# a202-4-band-eq.net
KiCad netlist of a schematic drawn in EAGLE
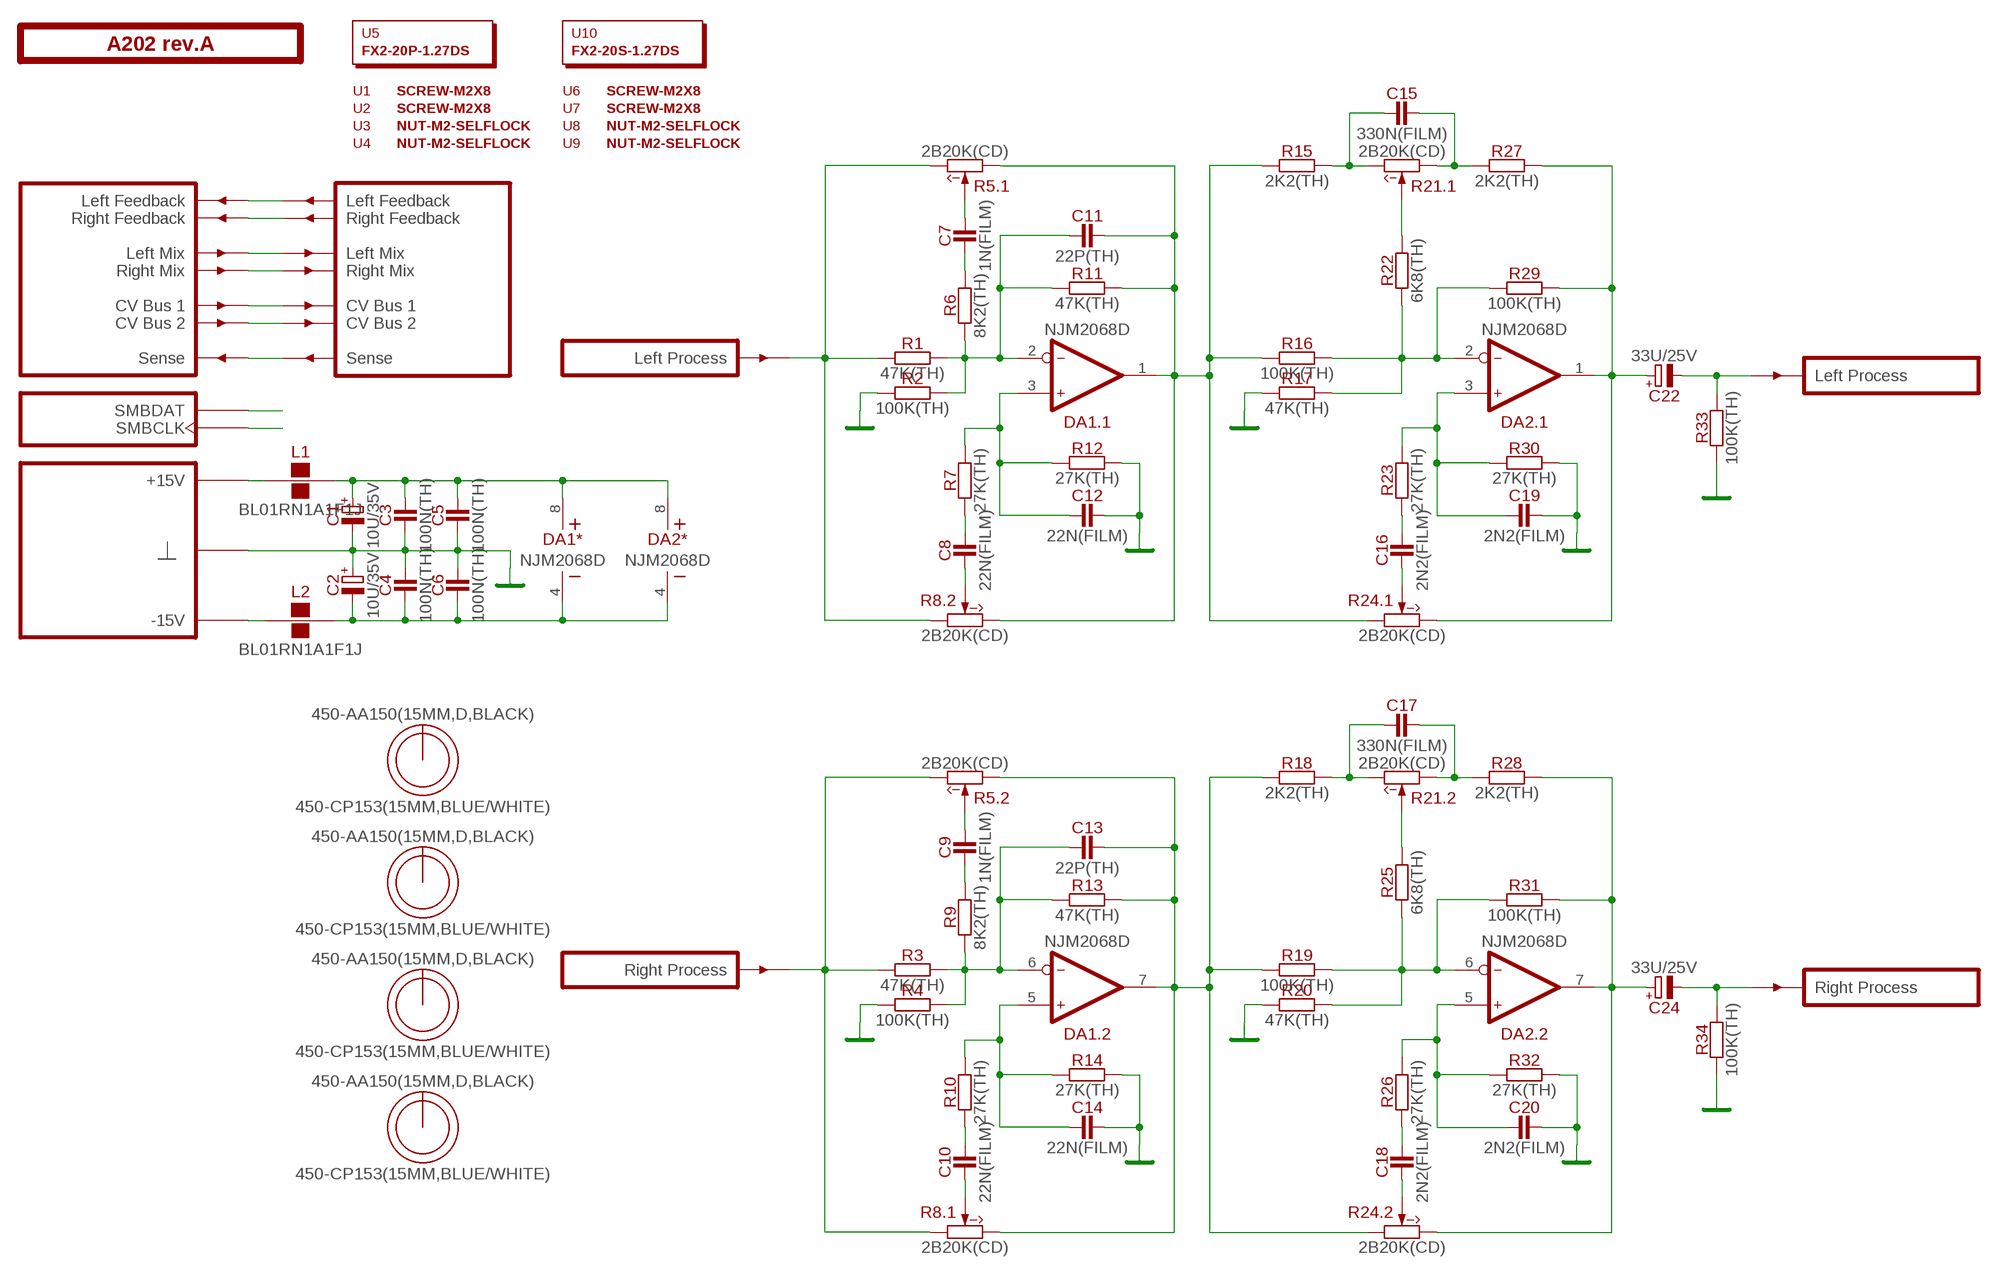
[diagram p0: schematic, sheet 1]

(export (version "E")
  (design (tool "Eeschema 10.0.6"))
  (components
    (comp (ref "C1")
      (value "10U/35V")
      (footprint "eagle-import:E2-5")
      (libsource (lib "eagle-import") (part "?10U/35V"))
    )
    (comp (ref "C2")
      (value "10U/35V")
      (footprint "eagle-import:E2-5")
      (libsource (lib "eagle-import") (part "?10U/35V"))
    )
    (comp (ref "C3")
      (value "100N(TH)")
      (footprint "eagle-import:C050-024X044")
      (libsource (lib "eagle-import") (part "?100N(TH)"))
    )
    (comp (ref "C4")
      (value "100N(TH)")
      (footprint "eagle-import:C050-024X044")
      (libsource (lib "eagle-import") (part "?100N(TH)"))
    )
    (comp (ref "C5")
      (value "100N(TH)")
      (footprint "eagle-import:C050-024X044")
      (libsource (lib "eagle-import") (part "?100N(TH)"))
    )
    (comp (ref "C6")
      (value "100N(TH)")
      (footprint "eagle-import:C050-024X044")
      (libsource (lib "eagle-import") (part "?100N(TH)"))
    )
    (comp (ref "C7")
      (value "1N(FILM)")
      (footprint "eagle-import:C050-025X075")
      (libsource (lib "eagle-import") (part "?1N(FILM)"))
    )
    (comp (ref "C8")
      (value "22N(FILM)")
      (footprint "eagle-import:C050-025X075")
      (libsource (lib "eagle-import") (part "?22N(FILM)"))
    )
    (comp (ref "C9")
      (value "1N(FILM)")
      (footprint "eagle-import:C050-025X075")
      (libsource (lib "eagle-import") (part "?1N(FILM)"))
    )
    (comp (ref "C10")
      (value "22N(FILM)")
      (footprint "eagle-import:C050-025X075")
      (libsource (lib "eagle-import") (part "?22N(FILM)"))
    )
    (comp (ref "C11")
      (value "22P(TH)")
      (footprint "eagle-import:C050-024X044")
      (libsource (lib "eagle-import") (part "?22P(TH)"))
    )
    (comp (ref "C12")
      (value "22N(FILM)")
      (footprint "eagle-import:C050-025X075")
      (libsource (lib "eagle-import") (part "?22N(FILM)"))
    )
    (comp (ref "C13")
      (value "22P(TH)")
      (footprint "eagle-import:C050-024X044")
      (libsource (lib "eagle-import") (part "?22P(TH)"))
    )
    (comp (ref "C14")
      (value "22N(FILM)")
      (footprint "eagle-import:C050-025X075")
      (libsource (lib "eagle-import") (part "?22N(FILM)"))
    )
    (comp (ref "C15")
      (value "330N(FILM)")
      (footprint "eagle-import:C050-035X075")
      (libsource (lib "eagle-import") (part "?330N(FILM)"))
    )
    (comp (ref "C16")
      (value "2N2(FILM)")
      (footprint "eagle-import:C050-025X075")
      (libsource (lib "eagle-import") (part "?2N2(FILM)"))
    )
    (comp (ref "C17")
      (value "330N(FILM)")
      (footprint "eagle-import:C050-035X075")
      (libsource (lib "eagle-import") (part "?330N(FILM)"))
    )
    (comp (ref "C18")
      (value "2N2(FILM)")
      (footprint "eagle-import:C050-025X075")
      (libsource (lib "eagle-import") (part "?2N2(FILM)"))
    )
    (comp (ref "C19")
      (value "2N2(FILM)")
      (footprint "eagle-import:C050-025X075")
      (libsource (lib "eagle-import") (part "?2N2(FILM)"))
    )
    (comp (ref "C20")
      (value "2N2(FILM)")
      (footprint "eagle-import:C050-025X075")
      (libsource (lib "eagle-import") (part "?2N2(FILM)"))
    )
    (comp (ref "C22")
      (value "33U/25V")
      (footprint "eagle-import:E2,5-7")
      (libsource (lib "eagle-import") (part "?33U/25V"))
    )
    (comp (ref "C24")
      (value "33U/25V")
      (footprint "eagle-import:E2,5-7")
      (libsource (lib "eagle-import") (part "?33U/25V"))
    )
    (comp (ref "DA1")
      (value "NJM2068D")
      (footprint "eagle-import:DIP-8")
      (libsource (lib "eagle-import") (part "NJM2068D"))
    )
    (comp (ref "DA2")
      (value "NJM2068D")
      (footprint "eagle-import:DIP-8")
      (libsource (lib "eagle-import") (part "NJM2068D"))
    )
    (comp (ref "L1")
      (value "BL01RN1A1F1J")
      (footprint "eagle-import:BL01RN1A")
      (libsource (lib "eagle-import") (part "BL01RN1A?1F1J"))
    )
    (comp (ref "L2")
      (value "BL01RN1A1F1J")
      (footprint "eagle-import:BL01RN1A")
      (libsource (lib "eagle-import") (part "BL01RN1A?1F1J"))
    )
    (comp (ref "O1")
      (value "450-AA150(15MM,D,BLACK)")
      (footprint "eagle-import:EMPTY")
      (libsource (lib "eagle-import") (part "450-AA?150(15MM,D,BLACK)"))
    )
    (comp (ref "O2")
      (value "450-AA150(15MM,D,BLACK)")
      (footprint "eagle-import:EMPTY")
      (libsource (lib "eagle-import") (part "450-AA?150(15MM,D,BLACK)"))
    )
    (comp (ref "O3")
      (value "450-AA150(15MM,D,BLACK)")
      (footprint "eagle-import:EMPTY")
      (libsource (lib "eagle-import") (part "450-AA?150(15MM,D,BLACK)"))
    )
    (comp (ref "O4")
      (value "450-AA150(15MM,D,BLACK)")
      (footprint "eagle-import:EMPTY")
      (libsource (lib "eagle-import") (part "450-AA?150(15MM,D,BLACK)"))
    )
    (comp (ref "O5")
      (value "450-CP153(15MM,BLUE/WHITE)")
      (footprint "eagle-import:EMPTY")
      (libsource (lib "eagle-import") (part "450-C?P153(15MM,BLUE/WHITE)"))
    )
    (comp (ref "O6")
      (value "450-CP153(15MM,BLUE/WHITE)")
      (footprint "eagle-import:EMPTY")
      (libsource (lib "eagle-import") (part "450-C?P153(15MM,BLUE/WHITE)"))
    )
    (comp (ref "O7")
      (value "450-CP153(15MM,BLUE/WHITE)")
      (footprint "eagle-import:EMPTY")
      (libsource (lib "eagle-import") (part "450-C?P153(15MM,BLUE/WHITE)"))
    )
    (comp (ref "O8")
      (value "450-CP153(15MM,BLUE/WHITE)")
      (footprint "eagle-import:EMPTY")
      (libsource (lib "eagle-import") (part "450-C?P153(15MM,BLUE/WHITE)"))
    )
    (comp (ref "PCB1")
      (value "A202 rev.A")
      (footprint "eagle-import:ST2-BOARD-50")
      (libsource (lib "eagle-import") (part "ST2-BOARD-?50"))
    )
    (comp (ref "R1")
      (value "47K(TH)")
      (footprint "eagle-import:R-0207_10")
      (libsource (lib "eagle-import") (part "?47K(TH)"))
    )
    (comp (ref "R2")
      (value "100K(TH)")
      (footprint "eagle-import:R-0207_10")
      (libsource (lib "eagle-import") (part "?100K(TH)"))
    )
    (comp (ref "R3")
      (value "47K(TH)")
      (footprint "eagle-import:R-0207_10")
      (libsource (lib "eagle-import") (part "?47K(TH)"))
    )
    (comp (ref "R4")
      (value "100K(TH)")
      (footprint "eagle-import:R-0207_10")
      (libsource (lib "eagle-import") (part "?100K(TH)"))
    )
    (comp (ref "R5")
      (value "2B20K(CD)")
      (footprint "eagle-import:RV11-DUAL")
      (libsource (lib "eagle-import") (part "2?B20K(CD)"))
    )
    (comp (ref "R6")
      (value "8K2(TH)")
      (footprint "eagle-import:R-0207_10")
      (libsource (lib "eagle-import") (part "?8K2(TH)"))
    )
    (comp (ref "R7")
      (value "27K(TH)")
      (footprint "eagle-import:R-0207_10")
      (libsource (lib "eagle-import") (part "?27K(TH)"))
    )
    (comp (ref "R8")
      (value "2B20K(CD)")
      (footprint "eagle-import:RV11-DUAL")
      (libsource (lib "eagle-import") (part "2?B20K(CD)"))
    )
    (comp (ref "R9")
      (value "8K2(TH)")
      (footprint "eagle-import:R-0207_10")
      (libsource (lib "eagle-import") (part "?8K2(TH)"))
    )
    (comp (ref "R10")
      (value "27K(TH)")
      (footprint "eagle-import:R-0207_10")
      (libsource (lib "eagle-import") (part "?27K(TH)"))
    )
    (comp (ref "R11")
      (value "47K(TH)")
      (footprint "eagle-import:R-0207_10")
      (libsource (lib "eagle-import") (part "?47K(TH)"))
    )
    (comp (ref "R12")
      (value "27K(TH)")
      (footprint "eagle-import:R-0207_10")
      (libsource (lib "eagle-import") (part "?27K(TH)"))
    )
    (comp (ref "R13")
      (value "47K(TH)")
      (footprint "eagle-import:R-0207_10")
      (libsource (lib "eagle-import") (part "?47K(TH)"))
    )
    (comp (ref "R14")
      (value "27K(TH)")
      (footprint "eagle-import:R-0207_10")
      (libsource (lib "eagle-import") (part "?27K(TH)"))
    )
    (comp (ref "R15")
      (value "2K2(TH)")
      (footprint "eagle-import:R-0207_10")
      (libsource (lib "eagle-import") (part "?2K2(TH)"))
    )
    (comp (ref "R16")
      (value "100K(TH)")
      (footprint "eagle-import:R-0207_10")
      (libsource (lib "eagle-import") (part "?100K(TH)"))
    )
    (comp (ref "R17")
      (value "47K(TH)")
      (footprint "eagle-import:R-0207_10")
      (libsource (lib "eagle-import") (part "?47K(TH)"))
    )
    (comp (ref "R18")
      (value "2K2(TH)")
      (footprint "eagle-import:R-0207_10")
      (libsource (lib "eagle-import") (part "?2K2(TH)"))
    )
    (comp (ref "R19")
      (value "100K(TH)")
      (footprint "eagle-import:R-0207_10")
      (libsource (lib "eagle-import") (part "?100K(TH)"))
    )
    (comp (ref "R20")
      (value "47K(TH)")
      (footprint "eagle-import:R-0207_10")
      (libsource (lib "eagle-import") (part "?47K(TH)"))
    )
    (comp (ref "R21")
      (value "2B20K(CD)")
      (footprint "eagle-import:RV11-DUAL")
      (libsource (lib "eagle-import") (part "2?B20K(CD)"))
    )
    (comp (ref "R22")
      (value "6K8(TH)")
      (footprint "eagle-import:R-0207_10")
      (libsource (lib "eagle-import") (part "?6K8(TH)"))
    )
    (comp (ref "R23")
      (value "27K(TH)")
      (footprint "eagle-import:R-0207_10")
      (libsource (lib "eagle-import") (part "?27K(TH)"))
    )
    (comp (ref "R24")
      (value "2B20K(CD)")
      (footprint "eagle-import:RV11-DUAL")
      (libsource (lib "eagle-import") (part "2?B20K(CD)"))
    )
    (comp (ref "R25")
      (value "6K8(TH)")
      (footprint "eagle-import:R-0207_10")
      (libsource (lib "eagle-import") (part "?6K8(TH)"))
    )
    (comp (ref "R26")
      (value "27K(TH)")
      (footprint "eagle-import:R-0207_10")
      (libsource (lib "eagle-import") (part "?27K(TH)"))
    )
    (comp (ref "R27")
      (value "2K2(TH)")
      (footprint "eagle-import:R-0207_10")
      (libsource (lib "eagle-import") (part "?2K2(TH)"))
    )
    (comp (ref "R28")
      (value "2K2(TH)")
      (footprint "eagle-import:R-0207_10")
      (libsource (lib "eagle-import") (part "?2K2(TH)"))
    )
    (comp (ref "R29")
      (value "100K(TH)")
      (footprint "eagle-import:R-0207_10")
      (libsource (lib "eagle-import") (part "?100K(TH)"))
    )
    (comp (ref "R30")
      (value "27K(TH)")
      (footprint "eagle-import:R-0207_10")
      (libsource (lib "eagle-import") (part "?27K(TH)"))
    )
    (comp (ref "R31")
      (value "100K(TH)")
      (footprint "eagle-import:R-0207_10")
      (libsource (lib "eagle-import") (part "?100K(TH)"))
    )
    (comp (ref "R32")
      (value "27K(TH)")
      (footprint "eagle-import:R-0207_10")
      (libsource (lib "eagle-import") (part "?27K(TH)"))
    )
    (comp (ref "R33")
      (value "100K(TH)")
      (footprint "eagle-import:R-0207_10")
      (libsource (lib "eagle-import") (part "?100K(TH)"))
    )
    (comp (ref "R34")
      (value "100K(TH)")
      (footprint "eagle-import:R-0207_10")
      (libsource (lib "eagle-import") (part "?100K(TH)"))
    )
    (comp (ref "U1")
      (value "SCREW-M2X8")
      (footprint "eagle-import:EMPTY")
      (libsource (lib "eagle-import") (part "?SCREW-M2X8"))
    )
    (comp (ref "U2")
      (value "SCREW-M2X8")
      (footprint "eagle-import:EMPTY")
      (libsource (lib "eagle-import") (part "?SCREW-M2X8"))
    )
    (comp (ref "U3")
      (value "NUT-M2-SELFLOCK")
      (footprint "eagle-import:EMPTY")
      (libsource (lib "eagle-import") (part "?NUT-M2-SELFLOCK"))
    )
    (comp (ref "U4")
      (value "NUT-M2-SELFLOCK")
      (footprint "eagle-import:EMPTY")
      (libsource (lib "eagle-import") (part "?NUT-M2-SELFLOCK"))
    )
    (comp (ref "U5")
      (value "FX2-20P-1.27DS")
      (footprint "eagle-import:EMPTY")
      (libsource (lib "eagle-import") (part "?FX2-20P-1.27DS"))
    )
    (comp (ref "U6")
      (value "SCREW-M2X8")
      (footprint "eagle-import:EMPTY")
      (libsource (lib "eagle-import") (part "?SCREW-M2X8"))
    )
    (comp (ref "U7")
      (value "SCREW-M2X8")
      (footprint "eagle-import:EMPTY")
      (libsource (lib "eagle-import") (part "?SCREW-M2X8"))
    )
    (comp (ref "U8")
      (value "NUT-M2-SELFLOCK")
      (footprint "eagle-import:EMPTY")
      (libsource (lib "eagle-import") (part "?NUT-M2-SELFLOCK"))
    )
    (comp (ref "U9")
      (value "NUT-M2-SELFLOCK")
      (footprint "eagle-import:EMPTY")
      (libsource (lib "eagle-import") (part "?NUT-M2-SELFLOCK"))
    )
    (comp (ref "U10")
      (value "FX2-20S-1.27DS")
      (footprint "eagle-import:EMPTY")
      (libsource (lib "eagle-import") (part "?FX2-20S-1.27DS"))
    )
  )
  (nets
    (net (code "1") (name "GND") (class "Default")
      (node (ref "C1") (pin "-") (pinfunction "-_-") (pintype "passive"))
      (node (ref "C12") (pin "2") (pinfunction "2_2") (pintype "passive"))
      (node (ref "C14") (pin "2") (pinfunction "2_2") (pintype "passive"))
      (node (ref "C19") (pin "2") (pinfunction "2_2") (pintype "passive"))
      (node (ref "C2") (pin "+") (pinfunction "+_+") (pintype "passive"))
      (node (ref "C20") (pin "2") (pinfunction "2_2") (pintype "passive"))
      (node (ref "C3") (pin "1") (pinfunction "1_1") (pintype "passive"))
      (node (ref "C4") (pin "2") (pinfunction "2_2") (pintype "passive"))
      (node (ref "C5") (pin "1") (pinfunction "1_1") (pintype "passive"))
      (node (ref "C6") (pin "2") (pinfunction "2_2") (pintype "passive"))
      (node (ref "PCB1") (pin "B4") (pinfunction "GND_B4") (pintype "bidirectional"))
      (node (ref "PCB1") (pin "B4'") (pinfunction "GND_B4'") (pintype "bidirectional"))
      (node (ref "PCB1") (pin "B5") (pinfunction "GND_B5") (pintype "bidirectional"))
      (node (ref "PCB1") (pin "B5'") (pinfunction "GND_B5'") (pintype "bidirectional"))
      (node (ref "PCB1") (pin "B6") (pinfunction "GND_B6") (pintype "bidirectional"))
      (node (ref "PCB1") (pin "B6'") (pinfunction "GND_B6'") (pintype "bidirectional"))
      (node (ref "PCB1") (pin "B7") (pinfunction "GND_B7") (pintype "bidirectional"))
      (node (ref "PCB1") (pin "B7'") (pinfunction "GND_B7'") (pintype "bidirectional"))
      (node (ref "PCB1") (pin "B8") (pinfunction "GND_B8") (pintype "bidirectional"))
      (node (ref "PCB1") (pin "B8'") (pinfunction "GND_B8'") (pintype "bidirectional"))
      (node (ref "R12") (pin "2") (pinfunction "2_2") (pintype "passive"))
      (node (ref "R14") (pin "2") (pinfunction "2_2") (pintype "passive"))
      (node (ref "R17") (pin "1") (pinfunction "1_1") (pintype "passive"))
      (node (ref "R2") (pin "1") (pinfunction "1_1") (pintype "passive"))
      (node (ref "R20") (pin "1") (pinfunction "1_1") (pintype "passive"))
      (node (ref "R30") (pin "2") (pinfunction "2_2") (pintype "passive"))
      (node (ref "R32") (pin "2") (pinfunction "2_2") (pintype "passive"))
      (node (ref "R33") (pin "1") (pinfunction "1_1") (pintype "passive"))
      (node (ref "R34") (pin "1") (pinfunction "1_1") (pintype "passive"))
      (node (ref "R4") (pin "1") (pinfunction "1_1") (pintype "passive"))
    )
    (net (code "2") (name "Net-(C7-Pad1)") (class "Default")
      (node (ref "C7") (pin "1") (pinfunction "1_1") (pintype "passive"))
      (node (ref "R6") (pin "2") (pinfunction "2_2") (pintype "passive"))
    )
    (net (code "3") (name "Net-(C8-Pad2)") (class "Default")
      (node (ref "C8") (pin "2") (pinfunction "2_2") (pintype "passive"))
      (node (ref "R7") (pin "1") (pinfunction "1_1") (pintype "passive"))
    )
    (net (code "4") (name "Net-(C9-Pad1)") (class "Default")
      (node (ref "C9") (pin "1") (pinfunction "1_1") (pintype "passive"))
      (node (ref "R9") (pin "2") (pinfunction "2_2") (pintype "passive"))
    )
    (net (code "5") (name "Net-(C10-Pad2)") (class "Default")
      (node (ref "C10") (pin "2") (pinfunction "2_2") (pintype "passive"))
      (node (ref "R10") (pin "1") (pinfunction "1_1") (pintype "passive"))
    )
    (net (code "6") (name "Net-(C16-Pad2)") (class "Default")
      (node (ref "C16") (pin "2") (pinfunction "2_2") (pintype "passive"))
      (node (ref "R23") (pin "1") (pinfunction "1_1") (pintype "passive"))
    )
    (net (code "7") (name "Net-(C18-Pad2)") (class "Default")
      (node (ref "C18") (pin "2") (pinfunction "2_2") (pintype "passive"))
      (node (ref "R26") (pin "1") (pinfunction "1_1") (pintype "passive"))
    )
    (net (code "8") (name "Net-(DA1A-V+)") (class "Default")
      (node (ref "C1") (pin "+") (pinfunction "+_+") (pintype "passive"))
      (node (ref "C3") (pin "2") (pinfunction "2_2") (pintype "passive"))
      (node (ref "C5") (pin "2") (pinfunction "2_2") (pintype "passive"))
      (node (ref "DA1") (pin "8") (pinfunction "V+_8") (pintype "power_in"))
      (node (ref "DA2") (pin "8") (pinfunction "V+_8") (pintype "power_in"))
      (node (ref "L1") (pin "2") (pinfunction "2_2") (pintype "passive"))
    )
    (net (code "9") (name "Net-(DA1A-V-)") (class "Default")
      (node (ref "C2") (pin "-") (pinfunction "-_-") (pintype "passive"))
      (node (ref "C4") (pin "1") (pinfunction "1_1") (pintype "passive"))
      (node (ref "C6") (pin "1") (pinfunction "1_1") (pintype "passive"))
      (node (ref "DA1") (pin "4") (pinfunction "V-_4") (pintype "power_in"))
      (node (ref "DA2") (pin "4") (pinfunction "V-_4") (pintype "power_in"))
      (node (ref "L2") (pin "2") (pinfunction "2_2") (pintype "passive"))
    )
    (net (code "10") (name "Net-(DA1B-IN+)") (class "Default")
      (node (ref "C12") (pin "1") (pinfunction "1_1") (pintype "passive"))
      (node (ref "DA1") (pin "3") (pinfunction "IN+_3") (pintype "input"))
      (node (ref "R12") (pin "1") (pinfunction "1_1") (pintype "passive"))
      (node (ref "R7") (pin "2") (pinfunction "2_2") (pintype "passive"))
    )
    (net (code "11") (name "Net-(DA1B-IN-)") (class "Default")
      (node (ref "C11") (pin "1") (pinfunction "1_1") (pintype "passive"))
      (node (ref "DA1") (pin "2") (pinfunction "IN-_2") (pintype "input"))
      (node (ref "R1") (pin "2") (pinfunction "2_2") (pintype "passive"))
      (node (ref "R11") (pin "1") (pinfunction "1_1") (pintype "passive"))
      (node (ref "R2") (pin "2") (pinfunction "2_2") (pintype "passive"))
      (node (ref "R6") (pin "1") (pinfunction "1_1") (pintype "passive"))
    )
    (net (code "12") (name "Net-(DA1B-OUT)") (class "Default")
      (node (ref "C11") (pin "2") (pinfunction "2_2") (pintype "passive"))
      (node (ref "DA1") (pin "1") (pinfunction "OUT_1") (pintype "output"))
      (node (ref "R11") (pin "2") (pinfunction "2_2") (pintype "passive"))
      (node (ref "R15") (pin "1") (pinfunction "1_1") (pintype "passive"))
      (node (ref "R16") (pin "1") (pinfunction "1_1") (pintype "passive"))
      (node (ref "R24") (pin "1") (pinfunction "CCW_1") (pintype "passive"))
      (node (ref "R5") (pin "1") (pinfunction "CCW_1") (pintype "passive"))
      (node (ref "R8") (pin "3'") (pinfunction "CW_3'") (pintype "passive"))
    )
    (net (code "13") (name "Net-(DA1C-IN+)") (class "Default")
      (node (ref "C14") (pin "1") (pinfunction "1_1") (pintype "passive"))
      (node (ref "DA1") (pin "5") (pinfunction "IN+_5") (pintype "input"))
      (node (ref "R10") (pin "2") (pinfunction "2_2") (pintype "passive"))
      (node (ref "R14") (pin "1") (pinfunction "1_1") (pintype "passive"))
    )
    (net (code "14") (name "Net-(DA1C-IN-)") (class "Default")
      (node (ref "C13") (pin "1") (pinfunction "1_1") (pintype "passive"))
      (node (ref "DA1") (pin "6") (pinfunction "IN-_6") (pintype "input"))
      (node (ref "R13") (pin "1") (pinfunction "1_1") (pintype "passive"))
      (node (ref "R3") (pin "2") (pinfunction "2_2") (pintype "passive"))
      (node (ref "R4") (pin "2") (pinfunction "2_2") (pintype "passive"))
      (node (ref "R9") (pin "1") (pinfunction "1_1") (pintype "passive"))
    )
    (net (code "15") (name "Net-(DA1C-OUT)") (class "Default")
      (node (ref "C13") (pin "2") (pinfunction "2_2") (pintype "passive"))
      (node (ref "DA1") (pin "7") (pinfunction "OUT_7") (pintype "output"))
      (node (ref "R13") (pin "2") (pinfunction "2_2") (pintype "passive"))
      (node (ref "R18") (pin "1") (pinfunction "1_1") (pintype "passive"))
      (node (ref "R19") (pin "1") (pinfunction "1_1") (pintype "passive"))
      (node (ref "R24") (pin "1'") (pinfunction "CCW_1'") (pintype "passive"))
      (node (ref "R5") (pin "1'") (pinfunction "CCW_1'") (pintype "passive"))
      (node (ref "R8") (pin "3") (pinfunction "CW_3") (pintype "passive"))
    )
    (net (code "16") (name "Net-(DA2B-IN+)") (class "Default")
      (node (ref "C19") (pin "1") (pinfunction "1_1") (pintype "passive"))
      (node (ref "DA2") (pin "3") (pinfunction "IN+_3") (pintype "input"))
      (node (ref "R23") (pin "2") (pinfunction "2_2") (pintype "passive"))
      (node (ref "R30") (pin "1") (pinfunction "1_1") (pintype "passive"))
    )
    (net (code "17") (name "Net-(DA2B-IN-)") (class "Default")
      (node (ref "DA2") (pin "2") (pinfunction "IN-_2") (pintype "input"))
      (node (ref "R16") (pin "2") (pinfunction "2_2") (pintype "passive"))
      (node (ref "R17") (pin "2") (pinfunction "2_2") (pintype "passive"))
      (node (ref "R22") (pin "1") (pinfunction "1_1") (pintype "passive"))
      (node (ref "R29") (pin "1") (pinfunction "1_1") (pintype "passive"))
    )
    (net (code "18") (name "Net-(DA2B-OUT)") (class "Default")
      (node (ref "C22") (pin "+") (pinfunction "+_+") (pintype "passive"))
      (node (ref "DA2") (pin "1") (pinfunction "OUT_1") (pintype "output"))
      (node (ref "R24") (pin "3") (pinfunction "CW_3") (pintype "passive"))
      (node (ref "R27") (pin "2") (pinfunction "2_2") (pintype "passive"))
      (node (ref "R29") (pin "2") (pinfunction "2_2") (pintype "passive"))
    )
    (net (code "19") (name "Net-(DA2C-IN+)") (class "Default")
      (node (ref "C20") (pin "1") (pinfunction "1_1") (pintype "passive"))
      (node (ref "DA2") (pin "5") (pinfunction "IN+_5") (pintype "input"))
      (node (ref "R26") (pin "2") (pinfunction "2_2") (pintype "passive"))
      (node (ref "R32") (pin "1") (pinfunction "1_1") (pintype "passive"))
    )
    (net (code "20") (name "Net-(DA2C-IN-)") (class "Default")
      (node (ref "DA2") (pin "6") (pinfunction "IN-_6") (pintype "input"))
      (node (ref "R19") (pin "2") (pinfunction "2_2") (pintype "passive"))
      (node (ref "R20") (pin "2") (pinfunction "2_2") (pintype "passive"))
      (node (ref "R25") (pin "1") (pinfunction "1_1") (pintype "passive"))
      (node (ref "R31") (pin "1") (pinfunction "1_1") (pintype "passive"))
    )
    (net (code "21") (name "Net-(DA2C-OUT)") (class "Default")
      (node (ref "C24") (pin "+") (pinfunction "+_+") (pintype "passive"))
      (node (ref "DA2") (pin "7") (pinfunction "OUT_7") (pintype "output"))
      (node (ref "R24") (pin "3'") (pinfunction "CW_3'") (pintype "passive"))
      (node (ref "R28") (pin "2") (pinfunction "2_2") (pintype "passive"))
      (node (ref "R31") (pin "2") (pinfunction "2_2") (pintype "passive"))
    )
    (net (code "22") (name "Net-(L1-Pad1)") (class "Default")
      (node (ref "L1") (pin "1") (pinfunction "1_1") (pintype "passive"))
      (node (ref "PCB1") (pin "A+15") (pinfunction "P+15V_A+15") (pintype "bidirectional"))
      (node (ref "PCB1") (pin "A+15'") (pinfunction "P+15V_A+15'") (pintype "bidirectional"))
      (node (ref "PCB1") (pin "B+15") (pinfunction "P+15V_B+15") (pintype "bidirectional"))
      (node (ref "PCB1") (pin "B+15'") (pinfunction "P+15V_B+15'") (pintype "bidirectional"))
    )
    (net (code "23") (name "Net-(L2-Pad1)") (class "Default")
      (node (ref "L2") (pin "1") (pinfunction "1_1") (pintype "passive"))
      (node (ref "PCB1") (pin "A-15") (pinfunction "P-15V_A-15") (pintype "bidirectional"))
      (node (ref "PCB1") (pin "A-15'") (pinfunction "P-15V_A-15'") (pintype "bidirectional"))
      (node (ref "PCB1") (pin "B-15") (pinfunction "P-15V_B-15") (pintype "bidirectional"))
      (node (ref "PCB1") (pin "B-15'") (pinfunction "P-15V_B-15'") (pintype "bidirectional"))
    )
    (net (code "24") (name "Net-(PCB1B-INL)") (class "Default")
      (node (ref "PCB1") (pin "BINL") (pinfunction "INL_BINL") (pintype "bidirectional"))
      (node (ref "R1") (pin "1") (pinfunction "1_1") (pintype "passive"))
      (node (ref "R5") (pin "3") (pinfunction "CW_3") (pintype "passive"))
      (node (ref "R8") (pin "1'") (pinfunction "CCW_1'") (pintype "passive"))
    )
    (net (code "25") (name "Net-(PCB1C-INR)") (class "Default")
      (node (ref "PCB1") (pin "BINR") (pinfunction "INR_BINR") (pintype "bidirectional"))
      (node (ref "R3") (pin "1") (pinfunction "1_1") (pintype "passive"))
      (node (ref "R5") (pin "3'") (pinfunction "CW_3'") (pintype "passive"))
      (node (ref "R8") (pin "1") (pinfunction "CCW_1") (pintype "passive"))
    )
    (net (code "26") (name "Net-(PCB1D-OUTL)") (class "Default")
      (node (ref "C22") (pin "-") (pinfunction "-_-") (pintype "passive"))
      (node (ref "PCB1") (pin "BOUTL'") (pinfunction "OUTL_BOUTL'") (pintype "bidirectional"))
      (node (ref "R33") (pin "2") (pinfunction "2_2") (pintype "passive"))
    )
    (net (code "27") (name "Net-(PCB1E-OUTR)") (class "Default")
      (node (ref "C24") (pin "-") (pinfunction "-_-") (pintype "passive"))
      (node (ref "PCB1") (pin "BOUTR'") (pinfunction "OUTR_BOUTR'") (pintype "bidirectional"))
      (node (ref "R34") (pin "2") (pinfunction "2_2") (pintype "passive"))
    )
    (net (code "28") (name "Net-(PCB1F-CV1)") (class "Default")
      (node (ref "PCB1") (pin "ACV1") (pinfunction "CV1_ACV1") (pintype "bidirectional"))
      (node (ref "PCB1") (pin "ACV1'") (pinfunction "CV1'_ACV1'") (pintype "bidirectional"))
    )
    (net (code "29") (name "Net-(PCB1F-CV2)") (class "Default")
      (node (ref "PCB1") (pin "ACV2") (pinfunction "CV2_ACV2") (pintype "bidirectional"))
      (node (ref "PCB1") (pin "ACV2'") (pinfunction "CV2'_ACV2'") (pintype "bidirectional"))
    )
    (net (code "30") (name "Net-(PCB1F-LFBK)") (class "Default")
      (node (ref "PCB1") (pin "ALFBK") (pinfunction "LFBK_ALFBK") (pintype "bidirectional"))
      (node (ref "PCB1") (pin "ALFBK'") (pinfunction "LFBK'_ALFBK'") (pintype "bidirectional"))
    )
    (net (code "31") (name "Net-(PCB1F-LMIX)") (class "Default")
      (node (ref "PCB1") (pin "ALMIX") (pinfunction "LMIX_ALMIX") (pintype "bidirectional"))
      (node (ref "PCB1") (pin "ALMIX'") (pinfunction "LMIX'_ALMIX'") (pintype "bidirectional"))
    )
    (net (code "32") (name "Net-(PCB1F-RFBK)") (class "Default")
      (node (ref "PCB1") (pin "ARFBK") (pinfunction "RFBK_ARFBK") (pintype "bidirectional"))
      (node (ref "PCB1") (pin "ARFBK'") (pinfunction "RFBK'_ARFBK'") (pintype "bidirectional"))
    )
    (net (code "33") (name "Net-(PCB1F-RMIX)") (class "Default")
      (node (ref "PCB1") (pin "ARMIX") (pinfunction "RMIX_ARMIX") (pintype "bidirectional"))
      (node (ref "PCB1") (pin "ARMIX'") (pinfunction "RMIX'_ARMIX'") (pintype "bidirectional"))
    )
    (net (code "34") (name "Net-(PCB1F-SENSE)") (class "Default")
      (node (ref "PCB1") (pin "BSENSE") (pinfunction "SENSE_BSENSE") (pintype "bidirectional"))
      (node (ref "PCB1") (pin "BSENSE'") (pinfunction "SENSE'_BSENSE'") (pintype "bidirectional"))
    )
    (net (code "35") (name "Net-(PCB1H-SMBCLK-PadASMBCLK')") (class "Default")
      (node (ref "PCB1") (pin "ASMBCLK") (pinfunction "SMBCLK_ASMBCLK") (pintype "bidirectional"))
      (node (ref "PCB1") (pin "ASMBCLK'") (pinfunction "SMBCLK_ASMBCLK'") (pintype "bidirectional"))
    )
    (net (code "36") (name "Net-(PCB1H-SMBDAT-PadASMBDAT')") (class "Default")
      (node (ref "PCB1") (pin "ASMBDAT") (pinfunction "SMBDAT_ASMBDAT") (pintype "bidirectional"))
      (node (ref "PCB1") (pin "ASMBDAT'") (pinfunction "SMBDAT_ASMBDAT'") (pintype "bidirectional"))
    )
    (net (code "37") (name "Net-(R5A-W)") (class "Default")
      (node (ref "C7") (pin "2") (pinfunction "2_2") (pintype "passive"))
      (node (ref "R5") (pin "2") (pinfunction "W_2") (pintype "passive"))
    )
    (net (code "38") (name "Net-(R5B-W)") (class "Default")
      (node (ref "C9") (pin "2") (pinfunction "2_2") (pintype "passive"))
      (node (ref "R5") (pin "2'") (pinfunction "W_2'") (pintype "passive"))
    )
    (net (code "39") (name "Net-(R8A-W)") (class "Default")
      (node (ref "C10") (pin "1") (pinfunction "1_1") (pintype "passive"))
      (node (ref "R8") (pin "2") (pinfunction "W_2") (pintype "passive"))
    )
    (net (code "40") (name "Net-(R8B-W)") (class "Default")
      (node (ref "C8") (pin "1") (pinfunction "1_1") (pintype "passive"))
      (node (ref "R8") (pin "2'") (pinfunction "W_2'") (pintype "passive"))
    )
    (net (code "41") (name "Net-(R21A-CCW)") (class "Default")
      (node (ref "C15") (pin "2") (pinfunction "2_2") (pintype "passive"))
      (node (ref "R21") (pin "1") (pinfunction "CCW_1") (pintype "passive"))
      (node (ref "R27") (pin "1") (pinfunction "1_1") (pintype "passive"))
    )
    (net (code "42") (name "Net-(R21A-CW)") (class "Default")
      (node (ref "C15") (pin "1") (pinfunction "1_1") (pintype "passive"))
      (node (ref "R15") (pin "2") (pinfunction "2_2") (pintype "passive"))
      (node (ref "R21") (pin "3") (pinfunction "CW_3") (pintype "passive"))
    )
    (net (code "43") (name "Net-(R21A-W)") (class "Default")
      (node (ref "R21") (pin "2") (pinfunction "W_2") (pintype "passive"))
      (node (ref "R22") (pin "2") (pinfunction "2_2") (pintype "passive"))
    )
    (net (code "44") (name "Net-(R21B-CCW)") (class "Default")
      (node (ref "C17") (pin "2") (pinfunction "2_2") (pintype "passive"))
      (node (ref "R21") (pin "1'") (pinfunction "CCW_1'") (pintype "passive"))
      (node (ref "R28") (pin "1") (pinfunction "1_1") (pintype "passive"))
    )
    (net (code "45") (name "Net-(R21B-CW)") (class "Default")
      (node (ref "C17") (pin "1") (pinfunction "1_1") (pintype "passive"))
      (node (ref "R18") (pin "2") (pinfunction "2_2") (pintype "passive"))
      (node (ref "R21") (pin "3'") (pinfunction "CW_3'") (pintype "passive"))
    )
    (net (code "46") (name "Net-(R21B-W)") (class "Default")
      (node (ref "R21") (pin "2'") (pinfunction "W_2'") (pintype "passive"))
      (node (ref "R25") (pin "2") (pinfunction "2_2") (pintype "passive"))
    )
    (net (code "47") (name "Net-(R24A-W)") (class "Default")
      (node (ref "C16") (pin "1") (pinfunction "1_1") (pintype "passive"))
      (node (ref "R24") (pin "2") (pinfunction "W_2") (pintype "passive"))
    )
    (net (code "48") (name "Net-(R24B-W)") (class "Default")
      (node (ref "C18") (pin "1") (pinfunction "1_1") (pintype "passive"))
      (node (ref "R24") (pin "2'") (pinfunction "W_2'") (pintype "passive"))
    )
  )
)
